# exynos-backpack.net
KiCad netlist of a schematic drawn in EAGLE
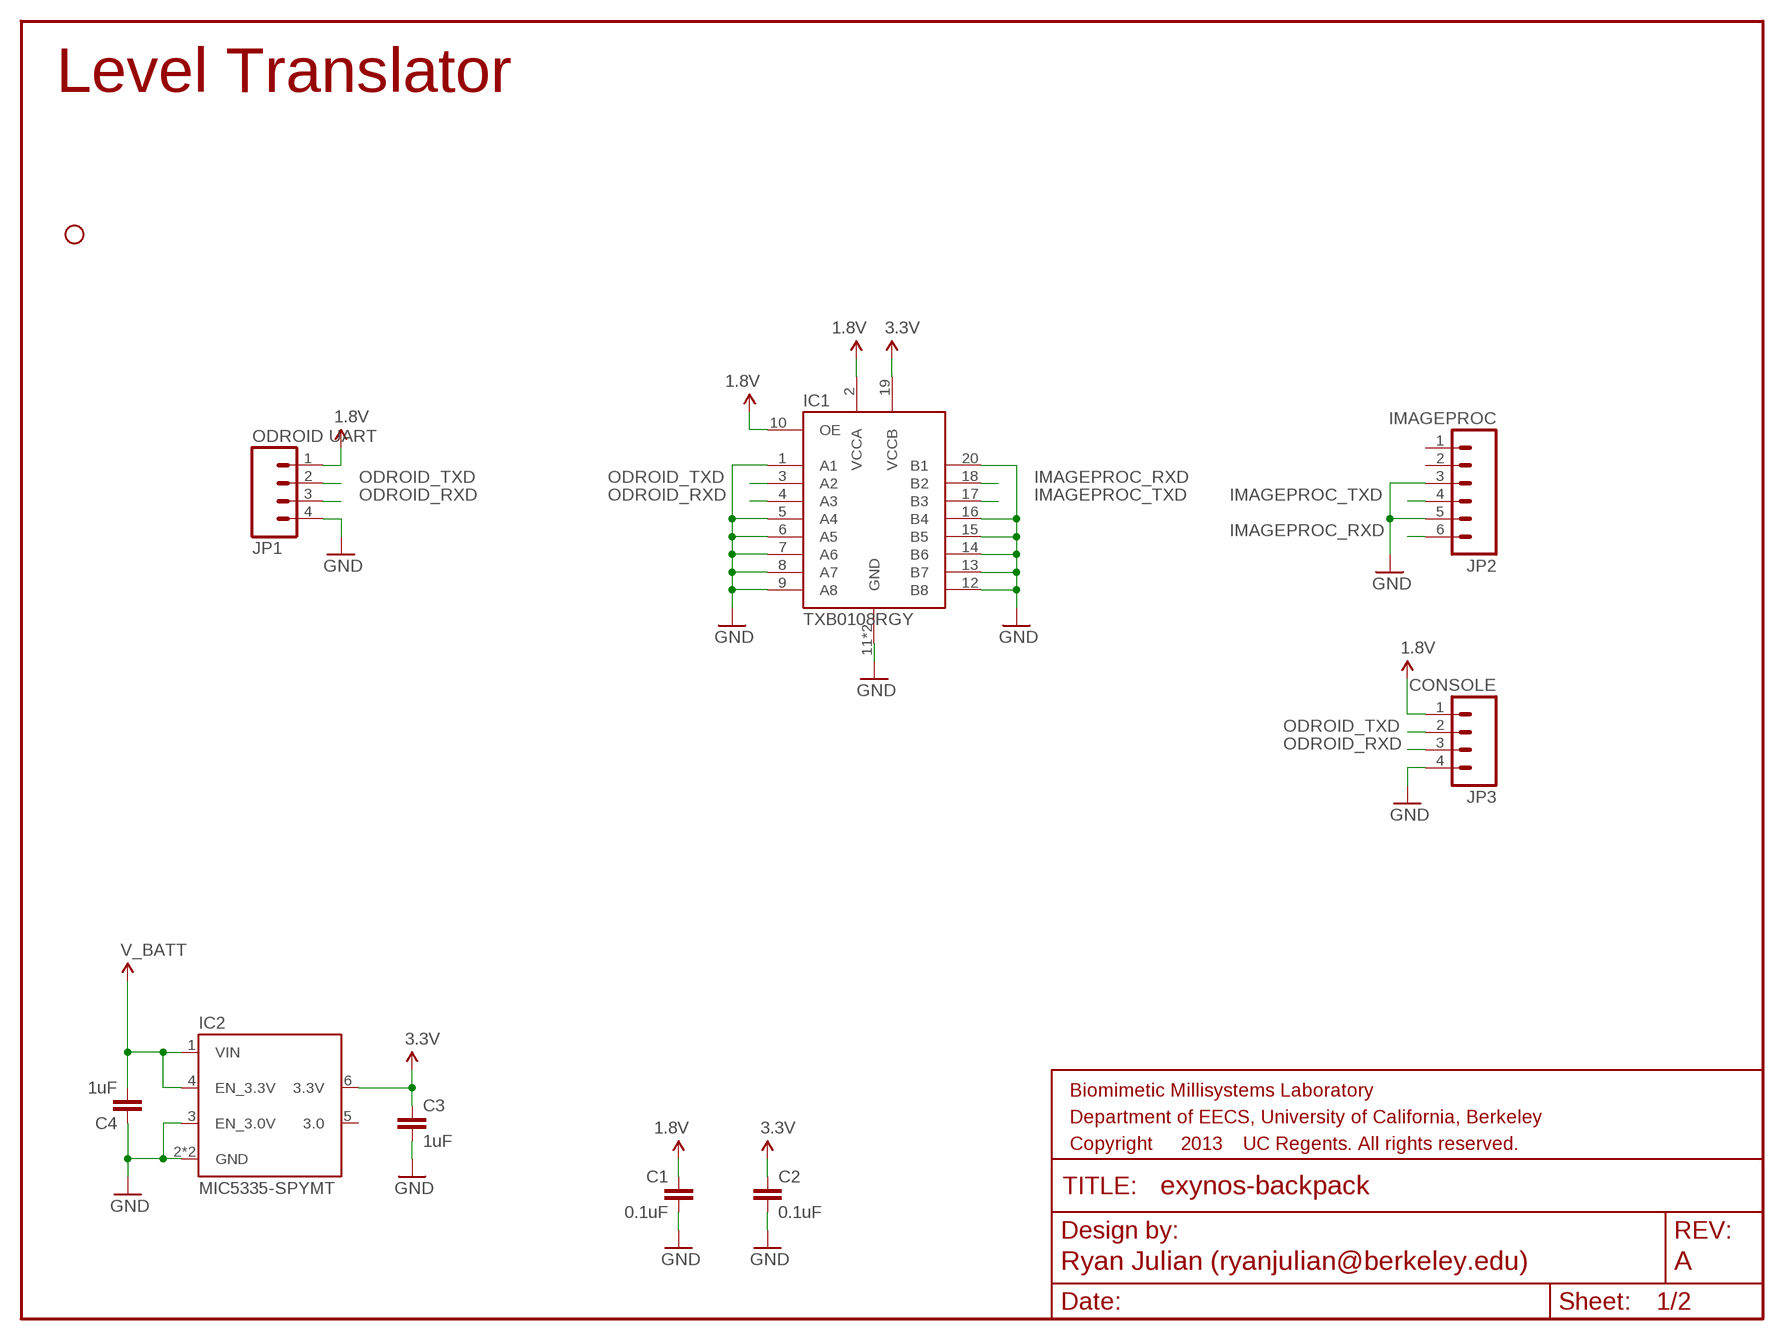
[diagram p0: schematic, sheet 1]
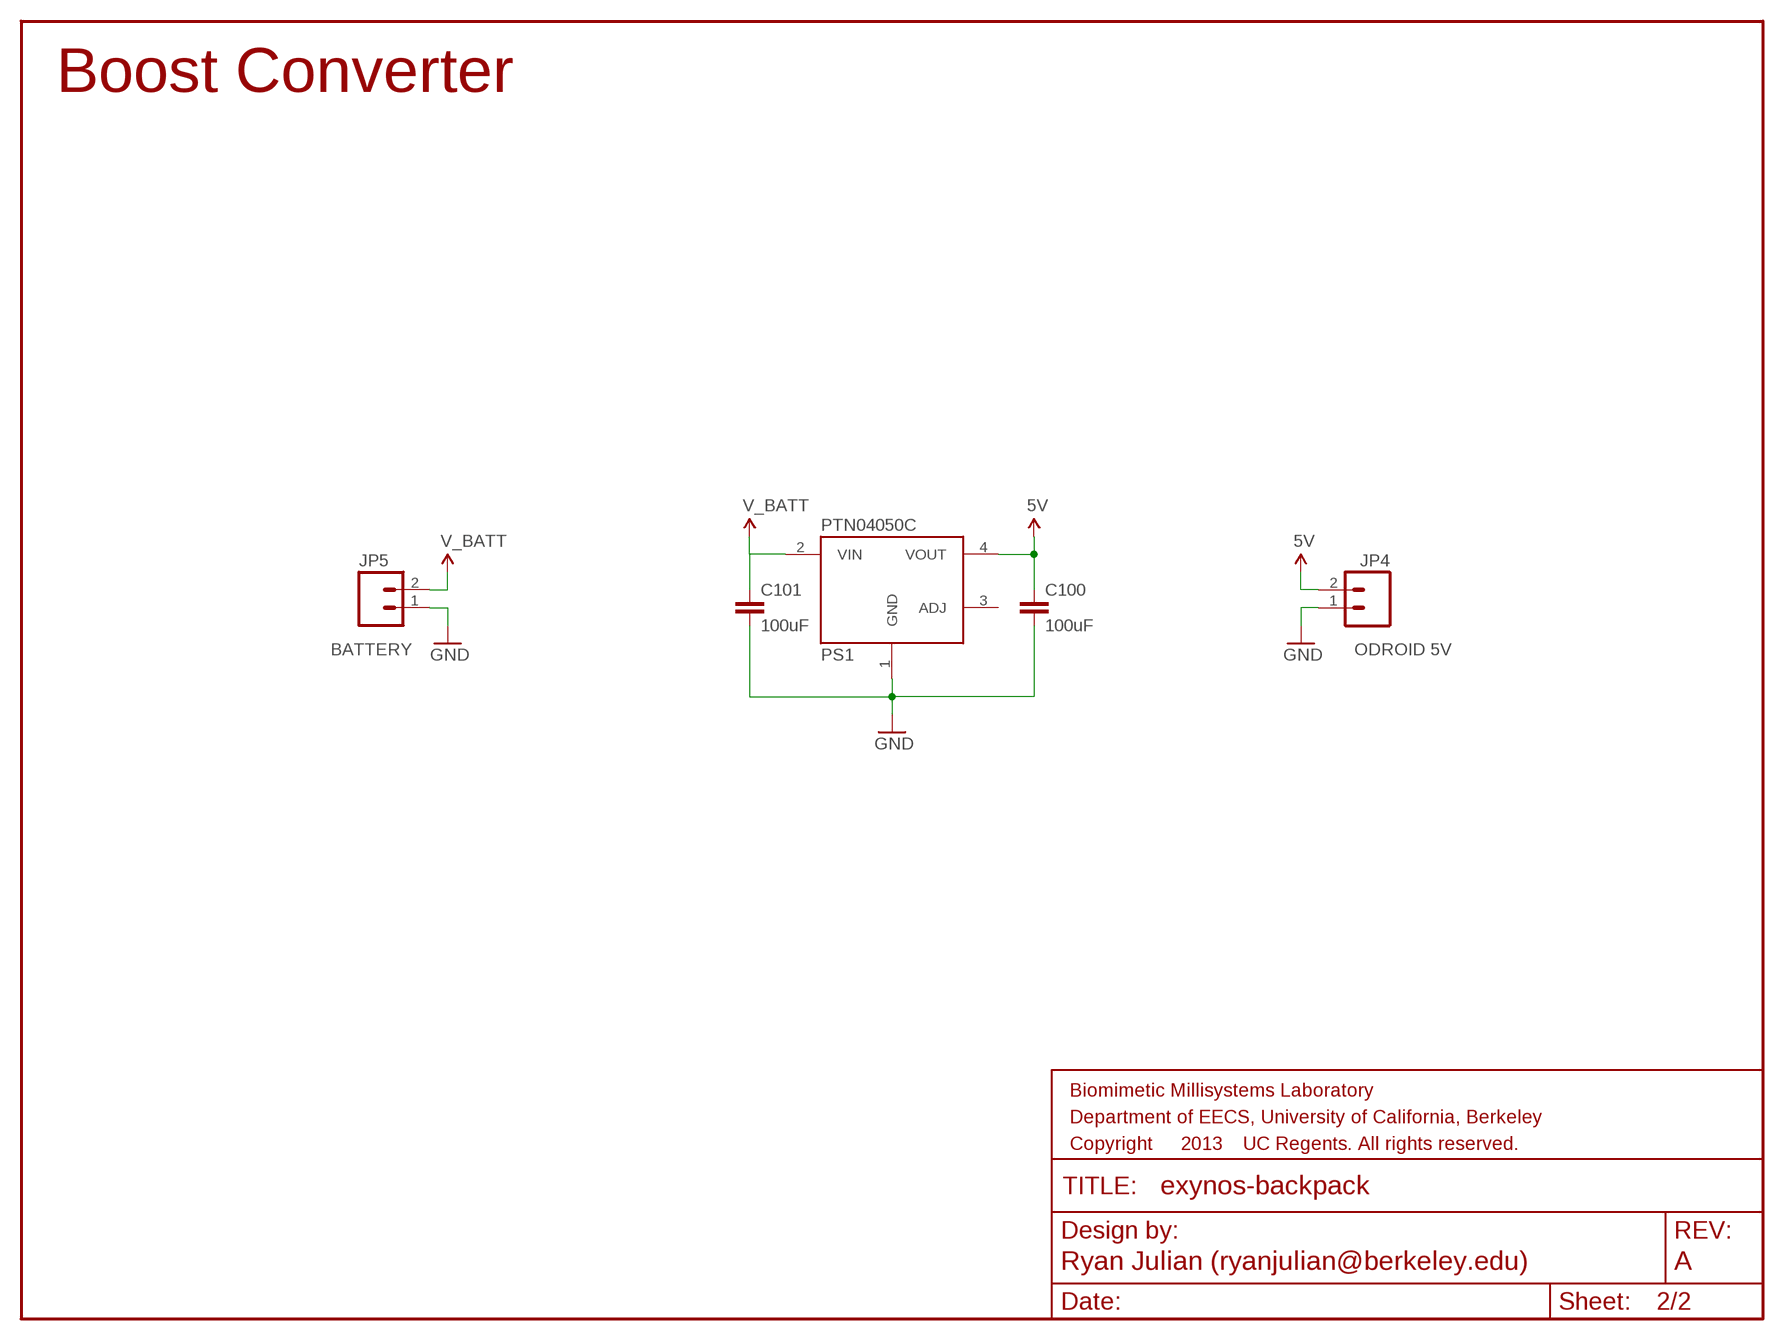
[diagram p1: schematic, sheet 2]

(export (version "E")
  (design (tool "Eeschema 10.0.6"))
  (components
    (comp (ref "C100")
      (value "100uF")
      (footprint "eagle-import:1210")
      (libsource (lib "eagle-import") (part "CAP1210"))
    )
    (comp (ref "C101")
      (value "100uF")
      (footprint "eagle-import:1210")
      (libsource (lib "eagle-import") (part "CAP1210"))
    )
    (comp (ref "JP4")
      (value "ODROID 5V")
      (footprint "eagle-import:JST-RCY-FEMALE_NOSILK")
      (libsource (lib "eagle-import") (part "JST-RCY-FEMALE-NOSILK"))
    )
    (comp (ref "JP5")
      (value "BATTERY")
      (footprint "eagle-import:JST-RCY-MALE_NOSILK")
      (libsource (lib "eagle-import") (part "JST-RCY-MALE-NOSILK"))
    )
    (comp (ref "PS1")
      (value "PTN04050C")
      (footprint "eagle-import:PTN04050C")
      (libsource (lib "eagle-import") (part "PTN04050C"))
    )
    (comp (ref "C1")
      (value "0.1uF")
      (footprint "eagle-import:0402-CAP")
      (libsource (lib "eagle-import") (part "CAP0402-CAP"))
    )
    (comp (ref "C2")
      (value "0.1uF")
      (footprint "eagle-import:0402-CAP")
      (libsource (lib "eagle-import") (part "CAP0402-CAP"))
    )
    (comp (ref "C3")
      (value "1uF")
      (footprint "eagle-import:0402-CAP")
      (libsource (lib "eagle-import") (part "CAP0402-CAP"))
    )
    (comp (ref "C4")
      (value "1uF")
      (footprint "eagle-import:0402-CAP")
      (libsource (lib "eagle-import") (part "CAP0402-CAP"))
    )
    (comp (ref "IC1")
      (value "TXB0108RGY")
      (footprint "eagle-import:R-PVQFN-N20")
      (libsource (lib "eagle-import") (part "TXB0108RGY"))
    )
    (comp (ref "IC2")
      (value "MIC5335-SPYMT")
      (footprint "eagle-import:MLF-6")
      (libsource (lib "eagle-import") (part "MIC5335-SPYMT"))
    )
    (comp (ref "JP1")
      (value "ODROID UART")
      (footprint "eagle-import:1X04_MOLEX_5267_NOSILK")
      (libsource (lib "eagle-import") (part "M041X04_MOLEX_5267_NOSILK"))
    )
    (comp (ref "JP2")
      (value "IMAGEPROC")
      (footprint "eagle-import:MOLEX_503480-0600")
      (libsource (lib "eagle-import") (part "MOLEX_503480-0600"))
    )
    (comp (ref "JP3")
      (value "CONSOLE")
      (footprint "eagle-import:1X04_MOLEX_5267")
      (libsource (lib "eagle-import") (part "M04MOLEX_5267"))
    )
    (comp (ref "U$2")
      (value "ODROID-U2")
      (footprint "eagle-import:ODROID-U2-KEEPOUT")
      (libsource (lib "eagle-import") (part "ODROID-U2"))
    )
  )
  (nets
    (net (code "1") (name "1.8V") (class "Default")
      (node (ref "C1") (pin "1") (pinfunction "1_1") (pintype "passive"))
      (node (ref "IC1") (pin "10") (pinfunction "OE_10") (pintype "bidirectional"))
      (node (ref "IC1") (pin "2") (pinfunction "VCCA_2") (pintype "bidirectional"))
      (node (ref "JP1") (pin "1") (pinfunction "1_1") (pintype "passive"))
      (node (ref "JP3") (pin "1") (pinfunction "1_1") (pintype "passive"))
    )
    (net (code "2") (name "3.3V") (class "Default")
      (node (ref "C2") (pin "1") (pinfunction "1_1") (pintype "passive"))
      (node (ref "C3") (pin "1") (pinfunction "1_1") (pintype "passive"))
      (node (ref "IC1") (pin "19") (pinfunction "VCCB_19") (pintype "bidirectional"))
      (node (ref "IC2") (pin "6") (pinfunction "3.3V_6") (pintype "bidirectional"))
    )
    (net (code "3") (name "5V") (class "Default")
      (node (ref "C100") (pin "1") (pinfunction "1_1") (pintype "passive"))
      (node (ref "JP4") (pin "2") (pinfunction "2_2") (pintype "passive"))
      (node (ref "PS1") (pin "4") (pinfunction "VOUT_4") (pintype "bidirectional"))
    )
    (net (code "4") (name "GND") (class "Default")
      (node (ref "C1") (pin "2") (pinfunction "2_2") (pintype "passive"))
      (node (ref "C100") (pin "2") (pinfunction "2_2") (pintype "passive"))
      (node (ref "C101") (pin "2") (pinfunction "2_2") (pintype "passive"))
      (node (ref "C2") (pin "2") (pinfunction "2_2") (pintype "passive"))
      (node (ref "C3") (pin "2") (pinfunction "2_2") (pintype "passive"))
      (node (ref "C4") (pin "1") (pinfunction "1_1") (pintype "passive"))
      (node (ref "IC1") (pin "1") (pinfunction "A1_1") (pintype "bidirectional"))
      (node (ref "IC1") (pin "11") (pinfunction "GND_11") (pintype "bidirectional"))
      (node (ref "IC1") (pin "12") (pinfunction "B8_12") (pintype "bidirectional"))
      (node (ref "IC1") (pin "13") (pinfunction "B7_13") (pintype "bidirectional"))
      (node (ref "IC1") (pin "14") (pinfunction "B6_14") (pintype "bidirectional"))
      (node (ref "IC1") (pin "15") (pinfunction "B5_15") (pintype "bidirectional"))
      (node (ref "IC1") (pin "16") (pinfunction "B4_16") (pintype "bidirectional"))
      (node (ref "IC1") (pin "20") (pinfunction "B1_20") (pintype "bidirectional"))
      (node (ref "IC1") (pin "5") (pinfunction "A4_5") (pintype "bidirectional"))
      (node (ref "IC1") (pin "6") (pinfunction "A5_6") (pintype "bidirectional"))
      (node (ref "IC1") (pin "7") (pinfunction "A6_7") (pintype "bidirectional"))
      (node (ref "IC1") (pin "8") (pinfunction "A7_8") (pintype "bidirectional"))
      (node (ref "IC1") (pin "9") (pinfunction "A8_9") (pintype "bidirectional"))
      (node (ref "IC1") (pin "EPAD") (pinfunction "GND_EPAD") (pintype "bidirectional"))
      (node (ref "IC2") (pin "2") (pinfunction "GND_2") (pintype "bidirectional"))
      (node (ref "IC2") (pin "3") (pinfunction "EN_3.0V_3") (pintype "bidirectional"))
      (node (ref "IC2") (pin "EPAD") (pinfunction "GND_EPAD") (pintype "bidirectional"))
      (node (ref "JP1") (pin "4") (pinfunction "4_4") (pintype "passive"))
      (node (ref "JP2") (pin "3") (pinfunction "3_3") (pintype "passive"))
      (node (ref "JP2") (pin "5") (pinfunction "5_5") (pintype "passive"))
      (node (ref "JP3") (pin "4") (pinfunction "4_4") (pintype "passive"))
      (node (ref "JP4") (pin "1") (pinfunction "1_1") (pintype "passive"))
      (node (ref "JP5") (pin "1") (pinfunction "1_1") (pintype "passive"))
      (node (ref "PS1") (pin "1") (pinfunction "GND_1") (pintype "bidirectional"))
    )
    (net (code "5") (name "IMAGEPROC_RXD") (class "Default")
      (node (ref "IC1") (pin "18") (pinfunction "B2_18") (pintype "bidirectional"))
      (node (ref "JP2") (pin "6") (pinfunction "6_6") (pintype "passive"))
    )
    (net (code "6") (name "IMAGEPROC_TXD") (class "Default")
      (node (ref "IC1") (pin "17") (pinfunction "B3_17") (pintype "bidirectional"))
      (node (ref "JP2") (pin "4") (pinfunction "4_4") (pintype "passive"))
    )
    (net (code "7") (name "ODROID_RXD") (class "Default")
      (node (ref "IC1") (pin "4") (pinfunction "A3_4") (pintype "bidirectional"))
      (node (ref "JP1") (pin "3") (pinfunction "3_3") (pintype "passive"))
      (node (ref "JP3") (pin "3") (pinfunction "3_3") (pintype "passive"))
    )
    (net (code "8") (name "ODROID_TXD") (class "Default")
      (node (ref "IC1") (pin "3") (pinfunction "A2_3") (pintype "bidirectional"))
      (node (ref "JP1") (pin "2") (pinfunction "2_2") (pintype "passive"))
      (node (ref "JP3") (pin "2") (pinfunction "2_2") (pintype "passive"))
    )
    (net (code "9") (name "V_BATT") (class "Default")
      (node (ref "C101") (pin "1") (pinfunction "1_1") (pintype "passive"))
      (node (ref "C4") (pin "2") (pinfunction "2_2") (pintype "passive"))
      (node (ref "IC2") (pin "1") (pinfunction "VIN_1") (pintype "bidirectional"))
      (node (ref "IC2") (pin "4") (pinfunction "EN_3.3V_4") (pintype "bidirectional"))
      (node (ref "JP5") (pin "2") (pinfunction "2_2") (pintype "passive"))
      (node (ref "PS1") (pin "2") (pinfunction "VIN_2") (pintype "bidirectional"))
    )
    (net (code "10") (name "unconnected-(IC2-3.0-Pad5)") (class "Default")
      (node (ref "IC2") (pin "5") (pinfunction "3.0_5") (pintype "bidirectional"))
    )
    (net (code "11") (name "unconnected-(JP2-Pad1)") (class "Default")
      (node (ref "JP2") (pin "1") (pinfunction "1_1") (pintype "passive"))
    )
    (net (code "12") (name "unconnected-(JP2-Pad2)") (class "Default")
      (node (ref "JP2") (pin "2") (pinfunction "2_2") (pintype "passive"))
    )
    (net (code "13") (name "unconnected-(PS1-ADJ-Pad3)") (class "Default")
      (node (ref "PS1") (pin "3") (pinfunction "ADJ_3") (pintype "bidirectional"))
    )
  )
)
